# 6_-Interface_CAN.net
KiCad netlist of a schematic drawn in Altium Designer
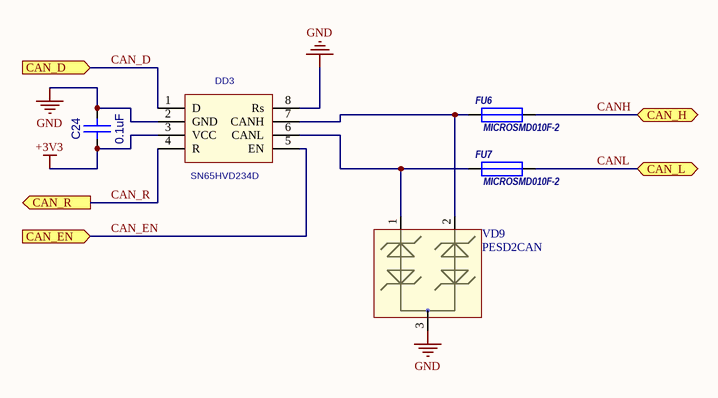
[diagram p0: [6]-Interface_CAN.SchDoc]

(export (version "E")
  (design (tool "Eeschema 10.0.6"))
  (components
    (comp (ref "C24")
      (value "0.1uF")
      (footprint "CC0603")
      (description "CC0603")
      (libsource (lib "gprs_modem_2") (part "CC0603"))
    )
    (comp (ref "DD3")
      (value "SN65HVD234D")
      (footprint "SO-8")
      (description "CAN Transceiver")
      (libsource (lib "gprs_modem_2") (part "SN65HVD234D"))
    )
    (comp (ref "FU6")
      (value "MICROSMD010F-2")
      (footprint "RC1210")
      (description "MICROSMD")
      (libsource (lib "gprs_modem_2") (part "MICROSMD"))
    )
    (comp (ref "FU7")
      (value "MICROSMD010F-2")
      (footprint "RC1210")
      (description "MICROSMD")
      (libsource (lib "gprs_modem_2") (part "MICROSMD"))
    )
    (comp (ref "VD9")
      (value "PESD2CAN")
      (footprint "SOT-23(123)")
      (description "TVS for CAN")
      (libsource (lib "gprs_modem_2") (part "PESD2CAN"))
    )
  )
  (nets
    (net (code "1") (name "+3V3") (class "Default")
      (node (ref "C24") (pin "1") (pinfunction "A_1") (pintype "passive"))
      (node (ref "DD3") (pin "3") (pinfunction "VCC_3") (pintype "passive"))
    )
    (net (code "2") (name "/CANH") (class "Default") (node (ref "FU6") (pin "2") (pintype "passive")))
    (net (code "3") (name "/CANL") (class "Default") (node (ref "FU7") (pin "2") (pintype "passive")))
    (net (code "4") (name "/CAN_D") (class "Default")
      (node (ref "DD3") (pin "1") (pinfunction "D_1") (pintype "passive"))
    )
    (net (code "5") (name "/CAN_EN") (class "Default")
      (node (ref "DD3") (pin "5") (pinfunction "EN_5") (pintype "passive"))
    )
    (net (code "6") (name "/CAN_R") (class "Default")
      (node (ref "DD3") (pin "4") (pinfunction "R_4") (pintype "passive"))
    )
    (net (code "7") (name "GND") (class "Default")
      (node (ref "C24") (pin "2") (pinfunction "B_2") (pintype "passive"))
      (node (ref "DD3") (pin "2") (pinfunction "GND_2") (pintype "passive"))
      (node (ref "DD3") (pin "8") (pinfunction "Rs_8") (pintype "passive"))
      (node (ref "VD9") (pin "3") (pinfunction "3_3") (pintype "passive"))
    )
    (net (code "8") (name "Net-(DD3-CANH)") (class "Default")
      (node (ref "DD3") (pin "7") (pinfunction "CANH_7") (pintype "passive"))
      (node (ref "FU6") (pin "1") (pintype "passive"))
      (node (ref "VD9") (pin "2") (pinfunction "2_2") (pintype "passive"))
    )
    (net (code "9") (name "Net-(DD3-CANL)") (class "Default")
      (node (ref "DD3") (pin "6") (pinfunction "CANL_6") (pintype "passive"))
      (node (ref "FU7") (pin "1") (pintype "passive"))
      (node (ref "VD9") (pin "1") (pinfunction "1_1") (pintype "passive"))
    )
  )
)
